# ESP32_-_Copy.net
KiCad netlist of a schematic drawn in EAGLE
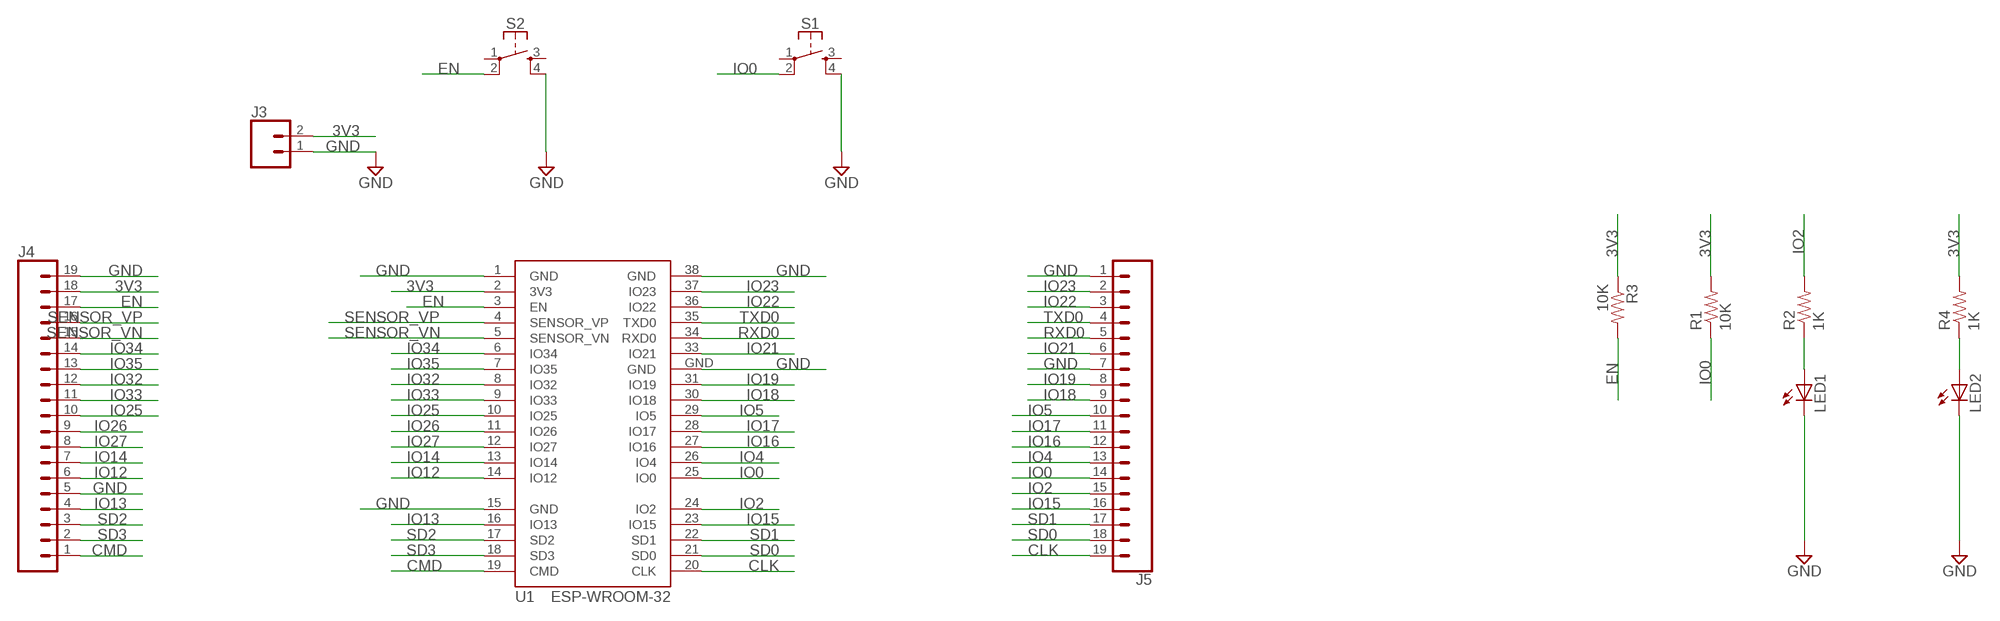
[diagram p0: schematic, sheet 1]

(export (version "E")
  (design (tool "Eeschema 10.0.6"))
  (components
    (comp (ref "J3")
      (value "CONN_02")
      (footprint "eagle-import:1X02")
      (libsource (lib "eagle-import") (part "CONN_02"))
    )
    (comp (ref "J4")
      (value "CONN_191X19_NO_SILK")
      (footprint "eagle-import:1X19_NO_SILK")
      (libsource (lib "eagle-import") (part "CONN_191X19_NO_SILK"))
    )
    (comp (ref "J5")
      (value "CONN_191X19_NO_SILK")
      (footprint "eagle-import:1X19_NO_SILK")
      (libsource (lib "eagle-import") (part "CONN_191X19_NO_SILK"))
    )
    (comp (ref "LED1")
      (value "LED5MM")
      (footprint "eagle-import:LED5MM")
      (libsource (lib "eagle-import") (part "LED5MM"))
    )
    (comp (ref "LED2")
      (value "LED5MM")
      (footprint "eagle-import:LED5MM")
      (libsource (lib "eagle-import") (part "LED5MM"))
    )
    (comp (ref "R1")
      (value "10K")
      (footprint "eagle-import:0207_10")
      (libsource (lib "eagle-import") (part "R-US_0207/10"))
    )
    (comp (ref "R2")
      (value "1K")
      (footprint "eagle-import:0207_10")
      (libsource (lib "eagle-import") (part "R-US_0207/10"))
    )
    (comp (ref "R3")
      (value "10K")
      (footprint "eagle-import:0207_10")
      (libsource (lib "eagle-import") (part "R-US_0207/10"))
    )
    (comp (ref "R4")
      (value "1K")
      (footprint "eagle-import:0207_10")
      (libsource (lib "eagle-import") (part "R-US_0207/10"))
    )
    (comp (ref "S1")
      (value "MOMENTARY-SWITCH-SPST-2-SMD-5.2MM-TALL")
      (footprint "eagle-import:TACTILE_SWITCH_SMD_5.2MM")
      (libsource (lib "eagle-import") (part "MOMENTARY-SWITCH-SPST-2-SMD-5.2MM-TALL"))
    )
    (comp (ref "S2")
      (value "MOMENTARY-SWITCH-SPST-2-SMD-5.2MM-TALL")
      (footprint "eagle-import:TACTILE_SWITCH_SMD_5.2MM")
      (libsource (lib "eagle-import") (part "MOMENTARY-SWITCH-SPST-2-SMD-5.2MM-TALL"))
    )
    (comp (ref "U1")
      (value "ESP-WROOM-32")
      (footprint "eagle-import:ESP-WROOM-32")
      (libsource (lib "eagle-import") (part "ESP-WROOM-32"))
    )
  )
  (nets
    (net (code "1") (name "/3V3") (class "Default")
      (node (ref "J3") (pin "2") (pinfunction "2_2") (pintype "passive"))
      (node (ref "J4") (pin "18") (pinfunction "18_18") (pintype "passive"))
      (node (ref "R1") (pin "2") (pinfunction "2_2") (pintype "passive"))
      (node (ref "R3") (pin "1") (pinfunction "1_1") (pintype "passive"))
      (node (ref "R4") (pin "2") (pinfunction "2_2") (pintype "passive"))
      (node (ref "U1") (pin "2") (pinfunction "3V3_2") (pintype "power_in"))
    )
    (net (code "2") (name "/CLK") (class "Default")
      (node (ref "J5") (pin "19") (pinfunction "19_19") (pintype "passive"))
      (node (ref "U1") (pin "20") (pinfunction "CLK_20") (pintype "bidirectional"))
    )
    (net (code "3") (name "/CMD") (class "Default")
      (node (ref "J4") (pin "1") (pinfunction "1_1") (pintype "passive"))
      (node (ref "U1") (pin "19") (pinfunction "CMD_19") (pintype "bidirectional"))
    )
    (net (code "4") (name "/EN") (class "Default")
      (node (ref "J4") (pin "17") (pinfunction "17_17") (pintype "passive"))
      (node (ref "R3") (pin "2") (pinfunction "2_2") (pintype "passive"))
      (node (ref "S2") (pin "2") (pinfunction "2_2") (pintype "passive"))
      (node (ref "U1") (pin "3") (pinfunction "EN_3") (pintype "input"))
    )
    (net (code "5") (name "/IO0") (class "Default")
      (node (ref "J5") (pin "14") (pinfunction "14_14") (pintype "passive"))
      (node (ref "R1") (pin "1") (pinfunction "1_1") (pintype "passive"))
      (node (ref "S1") (pin "2") (pinfunction "2_2") (pintype "passive"))
      (node (ref "U1") (pin "25") (pinfunction "IO0_25") (pintype "bidirectional"))
    )
    (net (code "6") (name "/IO2") (class "Default")
      (node (ref "J5") (pin "15") (pinfunction "15_15") (pintype "passive"))
      (node (ref "R2") (pin "2") (pinfunction "2_2") (pintype "passive"))
      (node (ref "U1") (pin "24") (pinfunction "IO2_24") (pintype "bidirectional"))
    )
    (net (code "7") (name "/IO4") (class "Default")
      (node (ref "J5") (pin "13") (pinfunction "13_13") (pintype "passive"))
      (node (ref "U1") (pin "26") (pinfunction "IO4_26") (pintype "bidirectional"))
    )
    (net (code "8") (name "/IO5") (class "Default")
      (node (ref "J5") (pin "10") (pinfunction "10_10") (pintype "passive"))
      (node (ref "U1") (pin "29") (pinfunction "IO5_29") (pintype "bidirectional"))
    )
    (net (code "9") (name "/IO12") (class "Default")
      (node (ref "J4") (pin "6") (pinfunction "6_6") (pintype "passive"))
      (node (ref "U1") (pin "14") (pinfunction "IO12_14") (pintype "bidirectional"))
    )
    (net (code "10") (name "/IO13") (class "Default")
      (node (ref "J4") (pin "4") (pinfunction "4_4") (pintype "passive"))
      (node (ref "U1") (pin "16") (pinfunction "IO13_16") (pintype "bidirectional"))
    )
    (net (code "11") (name "/IO14") (class "Default")
      (node (ref "J4") (pin "7") (pinfunction "7_7") (pintype "passive"))
      (node (ref "U1") (pin "13") (pinfunction "IO14_13") (pintype "bidirectional"))
    )
    (net (code "12") (name "/IO15") (class "Default")
      (node (ref "J5") (pin "16") (pinfunction "16_16") (pintype "passive"))
      (node (ref "U1") (pin "23") (pinfunction "IO15_23") (pintype "bidirectional"))
    )
    (net (code "13") (name "/IO16") (class "Default")
      (node (ref "J5") (pin "12") (pinfunction "12_12") (pintype "passive"))
      (node (ref "U1") (pin "27") (pinfunction "IO16_27") (pintype "bidirectional"))
    )
    (net (code "14") (name "/IO17") (class "Default")
      (node (ref "J5") (pin "11") (pinfunction "11_11") (pintype "passive"))
      (node (ref "U1") (pin "28") (pinfunction "IO17_28") (pintype "bidirectional"))
    )
    (net (code "15") (name "/IO18") (class "Default")
      (node (ref "J5") (pin "9") (pinfunction "9_9") (pintype "passive"))
      (node (ref "U1") (pin "30") (pinfunction "IO18_30") (pintype "bidirectional"))
    )
    (net (code "16") (name "/IO19") (class "Default")
      (node (ref "J5") (pin "8") (pinfunction "8_8") (pintype "passive"))
      (node (ref "U1") (pin "31") (pinfunction "IO19_31") (pintype "bidirectional"))
    )
    (net (code "17") (name "/IO21") (class "Default")
      (node (ref "J5") (pin "6") (pinfunction "6_6") (pintype "passive"))
      (node (ref "U1") (pin "33") (pinfunction "IO21_33") (pintype "bidirectional"))
    )
    (net (code "18") (name "/IO22") (class "Default")
      (node (ref "J5") (pin "3") (pinfunction "3_3") (pintype "passive"))
      (node (ref "U1") (pin "36") (pinfunction "IO22_36") (pintype "bidirectional"))
    )
    (net (code "19") (name "/IO23") (class "Default")
      (node (ref "J5") (pin "2") (pinfunction "2_2") (pintype "passive"))
      (node (ref "U1") (pin "37") (pinfunction "IO23_37") (pintype "bidirectional"))
    )
    (net (code "20") (name "/IO25") (class "Default")
      (node (ref "J4") (pin "10") (pinfunction "10_10") (pintype "passive"))
      (node (ref "U1") (pin "10") (pinfunction "IO25_10") (pintype "bidirectional"))
    )
    (net (code "21") (name "/IO26") (class "Default")
      (node (ref "J4") (pin "9") (pinfunction "9_9") (pintype "passive"))
      (node (ref "U1") (pin "11") (pinfunction "IO26_11") (pintype "bidirectional"))
    )
    (net (code "22") (name "/IO27") (class "Default")
      (node (ref "J4") (pin "8") (pinfunction "8_8") (pintype "passive"))
      (node (ref "U1") (pin "12") (pinfunction "IO27_12") (pintype "bidirectional"))
    )
    (net (code "23") (name "/IO32") (class "Default")
      (node (ref "J4") (pin "12") (pinfunction "12_12") (pintype "passive"))
      (node (ref "U1") (pin "8") (pinfunction "IO32_8") (pintype "bidirectional"))
    )
    (net (code "24") (name "/IO33") (class "Default")
      (node (ref "J4") (pin "11") (pinfunction "11_11") (pintype "passive"))
      (node (ref "U1") (pin "9") (pinfunction "IO33_9") (pintype "bidirectional"))
    )
    (net (code "25") (name "/IO34") (class "Default")
      (node (ref "J4") (pin "14") (pinfunction "14_14") (pintype "passive"))
      (node (ref "U1") (pin "6") (pinfunction "IO34_6") (pintype "bidirectional"))
    )
    (net (code "26") (name "/IO35") (class "Default")
      (node (ref "J4") (pin "13") (pinfunction "13_13") (pintype "passive"))
      (node (ref "U1") (pin "7") (pinfunction "IO35_7") (pintype "bidirectional"))
    )
    (net (code "27") (name "/RXD0") (class "Default")
      (node (ref "J5") (pin "5") (pinfunction "5_5") (pintype "passive"))
      (node (ref "U1") (pin "34") (pinfunction "RXD0_34") (pintype "bidirectional"))
    )
    (net (code "28") (name "/SD0") (class "Default")
      (node (ref "J5") (pin "18") (pinfunction "18_18") (pintype "passive"))
      (node (ref "U1") (pin "21") (pinfunction "SD0_21") (pintype "bidirectional"))
    )
    (net (code "29") (name "/SD1") (class "Default")
      (node (ref "J5") (pin "17") (pinfunction "17_17") (pintype "passive"))
      (node (ref "U1") (pin "22") (pinfunction "SD1_22") (pintype "bidirectional"))
    )
    (net (code "30") (name "/SD2") (class "Default")
      (node (ref "J4") (pin "3") (pinfunction "3_3") (pintype "passive"))
      (node (ref "U1") (pin "17") (pinfunction "SD2_17") (pintype "bidirectional"))
    )
    (net (code "31") (name "/SD3") (class "Default")
      (node (ref "J4") (pin "2") (pinfunction "2_2") (pintype "passive"))
      (node (ref "U1") (pin "18") (pinfunction "SD3_18") (pintype "bidirectional"))
    )
    (net (code "32") (name "/SENSOR_VN") (class "Default")
      (node (ref "J4") (pin "15") (pinfunction "15_15") (pintype "passive"))
      (node (ref "U1") (pin "5") (pinfunction "SENSOR_VN_5") (pintype "bidirectional"))
    )
    (net (code "33") (name "/SENSOR_VP") (class "Default")
      (node (ref "J4") (pin "16") (pinfunction "16_16") (pintype "passive"))
      (node (ref "U1") (pin "4") (pinfunction "SENSOR_VP_4") (pintype "bidirectional"))
    )
    (net (code "34") (name "/TXD0") (class "Default")
      (node (ref "J5") (pin "4") (pinfunction "4_4") (pintype "passive"))
      (node (ref "U1") (pin "35") (pinfunction "TXD0_35") (pintype "bidirectional"))
    )
    (net (code "35") (name "GND") (class "Default")
      (node (ref "J3") (pin "1") (pinfunction "1_1") (pintype "passive"))
      (node (ref "J4") (pin "19") (pinfunction "19_19") (pintype "passive"))
      (node (ref "J4") (pin "5") (pinfunction "5_5") (pintype "passive"))
      (node (ref "J5") (pin "1") (pinfunction "1_1") (pintype "passive"))
      (node (ref "J5") (pin "7") (pinfunction "7_7") (pintype "passive"))
      (node (ref "LED1") (pin "K") (pinfunction "C_K") (pintype "passive"))
      (node (ref "LED2") (pin "K") (pinfunction "C_K") (pintype "passive"))
      (node (ref "S1") (pin "4") (pinfunction "4_4") (pintype "passive"))
      (node (ref "S2") (pin "4") (pinfunction "4_4") (pintype "passive"))
      (node (ref "U1") (pin "1") (pinfunction "GND_1") (pintype "power_in"))
      (node (ref "U1") (pin "15") (pinfunction "GND_15") (pintype "power_in"))
      (node (ref "U1") (pin "38") (pinfunction "GND_38") (pintype "power_in"))
      (node (ref "U1") (pin "GND") (pinfunction "GND_GND") (pintype "power_in"))
    )
    (net (code "36") (name "Net-(LED1-PadA)") (class "Default")
      (node (ref "LED1") (pin "A") (pinfunction "A_A") (pintype "passive"))
      (node (ref "R2") (pin "1") (pinfunction "1_1") (pintype "passive"))
    )
    (net (code "37") (name "Net-(LED2-PadA)") (class "Default")
      (node (ref "LED2") (pin "A") (pinfunction "A_A") (pintype "passive"))
      (node (ref "R4") (pin "1") (pinfunction "1_1") (pintype "passive"))
    )
    (net (code "38") (name "unconnected-(S1-Pad1)") (class "Default")
      (node (ref "S1") (pin "1") (pinfunction "1_1") (pintype "passive"))
    )
    (net (code "39") (name "unconnected-(S1-Pad3)") (class "Default")
      (node (ref "S1") (pin "3") (pinfunction "3_3") (pintype "passive"))
    )
    (net (code "40") (name "unconnected-(S2-Pad1)") (class "Default")
      (node (ref "S2") (pin "1") (pinfunction "1_1") (pintype "passive"))
    )
    (net (code "41") (name "unconnected-(S2-Pad3)") (class "Default")
      (node (ref "S2") (pin "3") (pinfunction "3_3") (pintype "passive"))
    )
  )
)
